# SeccionRF.net
KiCad netlist of a schematic drawn in Altium Designer
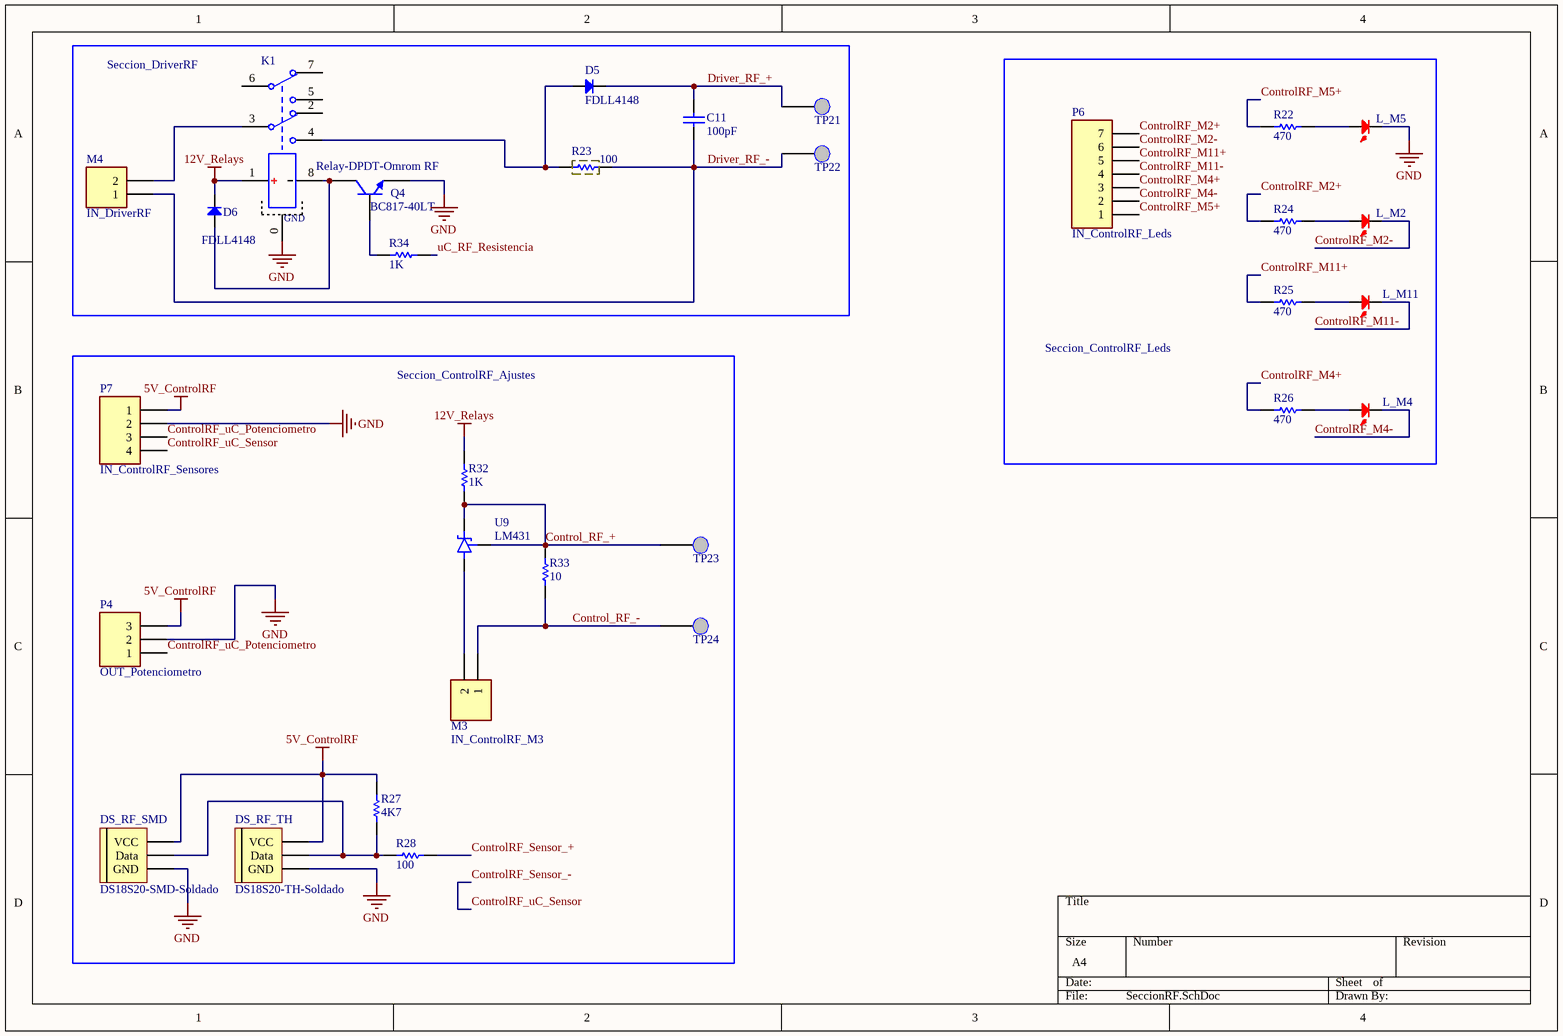
[diagram p0: SeccionRF.SchDoc]

(export (version "E")
  (design (tool "Eeschema 10.0.6"))
  (components
    (comp (ref "C11")
      (value "100pF")
      (footprint "Nahuel_SMD_Body:C_0805")
      (description "CAP CER 100PF 50V C0G/NP0 0805")
      (fields (field (name "PUBLISHER") "Altium Limited"))
      (libsource (lib "Nahuel_SMD_Body") (part "C_100pF"))
    )
    (comp (ref "D5")
      (value "FDLL4148")
      (footprint "Nahuel_SMD_Body:SOD-80/MLL34")
      (description "DIODE GEN PURP 100V 200MA LL34/SOD80/MINI MELF")
      (fields (field (name "PUBLISHER") "Altium Limited"))
      (libsource (lib "Nahuel_SMD_Body") (part "Diode FDLL4148"))
    )
    (comp (ref "D6")
      (value "FDLL4148")
      (footprint "SOD-80/MLL34")
      (description "DIODE GEN PURP 100V 200MA LL34/SOD80/MINI MELF")
      (fields (field (name "PUBLISHER") "Altium Limited"))
      (libsource (lib "Nahuel_SMD_Body") (part "Diode FDLL4148"))
    )
    (comp (ref "DS_RF_SMD")
      (value "DS18S20-SMD-Soldado")
      (footprint "Nahuel_SMD_Body:SOIC8")
      (description "SENSOR DIGITAL -55C-125C 8SOIC")
      (fields (field (name "PUBLISHER") "Altium Limited"))
      (libsource (lib "Nahuel_SMD_Body") (part "DS18S20-SMD-Soldado"))
    )
    (comp (ref "DS_RF_TH")
      (value "DS18S20-TH-Soldado")
      (footprint "Nahuel_TH_BODY:TO92")
      (description "Temperature Sensor Digital, Local -55°C ~ 125°C 8 b TO-92-3")
      (fields (field (name "PUBLISHER") "Altium Limited"))
      (libsource (lib "Nahuel_TH_BODY") (part "DS18S20-TH-Soldado"))
    )
    (comp (ref "K1")
      (value "Relay-DPDT-Omrom RF")
      (footprint "Nahuel_SMD_Body:Relay RF omron")
      (description "RELAY RF DPDT 1A 12V")
      (fields (field (name "PUBLISHER") "Altium Limited"))
      (libsource (lib "Nahuel_SMD_Body") (part "Relay-DPDT-Omrom RF"))
    )
    (comp (ref "L_M2")
      (value "PinesParaLed")
      (footprint "Nahuel_TH_BODY:Jumper-Simple")
      (description "CONN HEADER 2 POS 2.54")
      (fields (field (name "PUBLISHER") "Altium Limited"))
      (libsource (lib "Nahuel_TH_BODY") (part "PinesParaLed"))
    )
    (comp (ref "L_M4")
      (value "PinesParaLed")
      (footprint "Nahuel_TH_BODY:Jumper-Simple")
      (description "CONN HEADER 2 POS 2.54")
      (fields (field (name "PUBLISHER") "Altium Limited"))
      (libsource (lib "Nahuel_TH_BODY") (part "PinesParaLed"))
    )
    (comp (ref "L_M5")
      (value "PinesParaLed")
      (footprint "Nahuel_TH_BODY:Jumper-Simple")
      (description "CONN HEADER 2 POS 2.54")
      (fields (field (name "PUBLISHER") "Altium Limited"))
      (libsource (lib "Nahuel_TH_BODY") (part "PinesParaLed"))
    )
    (comp (ref "L_M11")
      (value "PinesParaLed")
      (footprint "Nahuel_TH_BODY:Jumper-Simple")
      (description "CONN HEADER 2 POS 2.54")
      (fields (field (name "PUBLISHER") "Altium Limited"))
      (libsource (lib "Nahuel_TH_BODY") (part "PinesParaLed"))
    )
    (comp (ref "M3")
      (value "IN_ControlRF_M3")
      (footprint "B2B-XH-A_3D")
      (description "CONN HEADER XH TOP 2POS 2.5MM")
      (fields (field (name "PUBLISHER") "Altium Limited"))
      (libsource (lib "") (part "JST_2.5_2_1"))
    )
    (comp (ref "M4")
      (value "IN_DriverRF")
      (footprint "B2B-XH-A_3D")
      (description "CONN HEADER XH TOP 2POS 2.5MM")
      (fields (field (name "PUBLISHER") "Altium Limited"))
      (libsource (lib "Nahuel_Connectors_BODY") (part "JST_2.5_2"))
    )
    (comp (ref "P4")
      (value "OUT_Potenciometro")
      (footprint "B3B-XH-A_3D")
      (description "CONN HEADER XH TOP 3POS 2.5MM")
      (fields (field (name "PUBLISHER") "Altium Limited"))
      (libsource (lib "Nahuel_Connectors_BODY") (part "JST_2.5_3"))
    )
    (comp (ref "P6")
      (value "IN_ControlRF_Leds")
      (footprint "Nahuel_Connectors_BODY:B7B-XH-A_3D")
      (description "CONN HEADER XH TOP 7POS 2.5MM")
      (fields (field (name "PUBLISHER") "Altium Limited"))
      (libsource (lib "Nahuel_Connectors_BODY") (part "JST_2.5_7"))
    )
    (comp (ref "P7")
      (value "IN_ControlRF_Sensores")
      (footprint "B4B-XH-A_3D")
      (description "CONN HEADER XH TOP 4POS 2.5MM")
      (fields (field (name "PUBLISHER") "Altium Limited"))
      (libsource (lib "Nahuel_Connectors_BODY") (part "JST_2.5_4"))
    )
    (comp (ref "Q4")
      (value "BC817-40LT")
      (footprint "Nahuel_SMD_Body:SOT23")
      (description "TRANS NPN 45V 0.5A SOT23")
      (fields (field (name "PUBLISHER") "Altium Limited"))
      (libsource (lib "Nahuel_SMD_Body") (part "BC817"))
    )
    (comp (ref "R22")
      (value "470")
      (footprint "Nahuel_SMD_Body:R_0805")
      (description "RES SMD 470 OHM 1% 1/8W 0805")
      (fields (field (name "PUBLISHER") "Altium Limited"))
      (libsource (lib "Nahuel_SMD_Body") (part "R_470"))
    )
    (comp (ref "R23")
      (value "100")
      (footprint "Nahuel_TH_BODY:R 10W")
      (description "RES 100 OHM 10W 5% AXIAL")
      (fields (field (name "PUBLISHER") "Altium Limited"))
      (libsource (lib "Nahuel_TH_BODY") (part "Resistor-10W"))
    )
    (comp (ref "R24")
      (value "470")
      (footprint "Nahuel_SMD_Body:R_0805")
      (description "RES SMD 470 OHM 1% 1/8W 0805")
      (fields (field (name "PUBLISHER") "Altium Limited"))
      (libsource (lib "Nahuel_SMD_Body") (part "R_470"))
    )
    (comp (ref "R25")
      (value "470")
      (footprint "Nahuel_SMD_Body:R_0805")
      (description "RES SMD 470 OHM 1% 1/8W 0805")
      (fields (field (name "PUBLISHER") "Altium Limited"))
      (libsource (lib "Nahuel_SMD_Body") (part "R_470"))
    )
    (comp (ref "R26")
      (value "470")
      (footprint "Nahuel_SMD_Body:R_0805")
      (description "RES SMD 470 OHM 1% 1/8W 0805")
      (fields (field (name "PUBLISHER") "Altium Limited"))
      (libsource (lib "Nahuel_SMD_Body") (part "R_470"))
    )
    (comp (ref "R27")
      (value "4K7")
      (footprint "Nahuel_SMD_Body:R_0805")
      (description "RES SMD 4K7 OHM 1% 1/8W 0805")
      (fields (field (name "PUBLISHER") "Altium Limited"))
      (libsource (lib "Nahuel_SMD_Body") (part "R_4k7"))
    )
    (comp (ref "R28")
      (value "100")
      (footprint "Nahuel_SMD_Body:R_0805")
      (description "RES SMD 100 OHM 1% 1/8W 0805")
      (fields (field (name "PUBLISHER") "Altium Limited"))
      (libsource (lib "Nahuel_SMD_Body") (part "R_100"))
    )
    (comp (ref "R32")
      (value "1K")
      (footprint "Nahuel_SMD_Body:R_0805")
      (description "RES SMD 1K OHM 1% 1/8W 0805")
      (fields (field (name "PUBLISHER") "Altium Limited"))
      (libsource (lib "Nahuel_SMD_Body") (part "R_1k"))
    )
    (comp (ref "R33")
      (value "10")
      (footprint "Nahuel_SMD_Body:R_0805")
      (description "RES SMD 10 OHM 1% 1/8W 0805")
      (fields (field (name "PUBLISHER") "Altium Limited"))
      (libsource (lib "Nahuel_SMD_Body") (part "R_10"))
    )
    (comp (ref "R34")
      (value "1K")
      (footprint "Nahuel_SMD_Body:R_0805")
      (description "RES SMD 1K OHM 1% 1/8W 0805")
      (fields (field (name "PUBLISHER") "Altium Limited"))
      (libsource (lib "Nahuel_SMD_Body") (part "R_1k"))
    )
    (comp (ref "TP21")
      (value "DRF+")
      (footprint "Nahuel_TH_BODY:TP-5002")
      (fields (field (name "PUBLISHER") "Altium Limited"))
      (libsource (lib "Nahuel_TH_BODY") (part "TestPoint"))
    )
    (comp (ref "TP22")
      (value "DRF-")
      (footprint "Nahuel_TH_BODY:TP-5002")
      (fields (field (name "PUBLISHER") "Altium Limited"))
      (libsource (lib "Nahuel_TH_BODY") (part "TestPoint"))
    )
    (comp (ref "TP23")
      (value "CRF+")
      (footprint "Nahuel_TH_BODY:TP-5002")
      (fields (field (name "PUBLISHER") "Altium Limited"))
      (libsource (lib "Nahuel_TH_BODY") (part "TestPoint"))
    )
    (comp (ref "TP24")
      (value "CRF-")
      (footprint "Nahuel_TH_BODY:TP-5002")
      (fields (field (name "PUBLISHER") "Altium Limited"))
      (libsource (lib "Nahuel_TH_BODY") (part "TestPoint"))
    )
    (comp (ref "U9")
      (value "LM431")
      (footprint "Nahuel_SMD_Body:SOT89")
      (description "IC VREF SHUNT 36V 1% SOT89-3")
      (fields (field (name "PUBLISHER") "Altium Limited"))
      (libsource (lib "Nahuel_SMD_Body") (part "LM431"))
    )
  )
  (nets
    (net (code "1") (name "/ControlRF_M2+") (class "Default")
      (node (ref "P6") (pin "7") (pinfunction "7_7") (pintype "passive"))
      (node (ref "R24") (pin "1") (pinfunction "1_1") (pintype "passive"))
    )
    (net (code "2") (name "/ControlRF_M2-") (class "Default")
      (node (ref "L_M2") (pin "2") (pinfunction "2_2") (pintype "passive"))
      (node (ref "P6") (pin "6") (pinfunction "6_6") (pintype "passive"))
    )
    (net (code "3") (name "/ControlRF_M4+") (class "Default")
      (node (ref "P6") (pin "3") (pinfunction "3_3") (pintype "passive"))
      (node (ref "R26") (pin "1") (pinfunction "1_1") (pintype "passive"))
    )
    (net (code "4") (name "/ControlRF_M4-") (class "Default")
      (node (ref "L_M4") (pin "2") (pinfunction "2_2") (pintype "passive"))
      (node (ref "P6") (pin "2") (pinfunction "2_2") (pintype "passive"))
    )
    (net (code "5") (name "/ControlRF_M5+") (class "Default")
      (node (ref "P6") (pin "1") (pinfunction "1_1") (pintype "passive"))
      (node (ref "R22") (pin "1") (pinfunction "1_1") (pintype "passive"))
    )
    (net (code "6") (name "/ControlRF_M11+") (class "Default")
      (node (ref "P6") (pin "5") (pinfunction "5_5") (pintype "passive"))
      (node (ref "R25") (pin "1") (pinfunction "1_1") (pintype "passive"))
    )
    (net (code "7") (name "/ControlRF_M11-") (class "Default")
      (node (ref "L_M11") (pin "2") (pinfunction "2_2") (pintype "passive"))
      (node (ref "P6") (pin "4") (pinfunction "4_4") (pintype "passive"))
    )
    (net (code "8") (name "/ControlRF_Sensor_+") (class "Default")
      (node (ref "R28") (pin "2") (pinfunction "2_2") (pintype "passive"))
    )
    (net (code "9") (name "/ControlRF_Sensor_-") (class "Default")
      (node (ref "P7") (pin "4") (pinfunction "4_4") (pintype "passive"))
    )
    (net (code "10") (name "/ControlRF_uC_Potenciometro") (class "Default")
      (node (ref "P4") (pin "1") (pinfunction "1_1") (pintype "passive"))
      (node (ref "P7") (pin "3") (pinfunction "3_3") (pintype "passive"))
    )
    (net (code "11") (name "/Control_RF_+") (class "Default")
      (node (ref "R32") (pin "1") (pinfunction "1_1") (pintype "passive"))
      (node (ref "R33") (pin "2") (pinfunction "2_2") (pintype "passive"))
      (node (ref "TP23") (pin "1") (pinfunction "1_1") (pintype "passive"))
      (node (ref "U9") (pin "1") (pinfunction "R_1") (pintype "passive"))
      (node (ref "U9") (pin "3") (pinfunction "K_3") (pintype "passive"))
    )
    (net (code "12") (name "/Control_RF_-") (class "Default")
      (node (ref "M3") (pin "1") (pinfunction "1_1") (pintype "passive"))
      (node (ref "R33") (pin "1") (pinfunction "1_1") (pintype "passive"))
      (node (ref "TP24") (pin "1") (pinfunction "1_1") (pintype "passive"))
    )
    (net (code "13") (name "/Driver_RF_+") (class "Default")
      (node (ref "C11") (pin "2") (pinfunction "2_2") (pintype "passive"))
      (node (ref "D5") (pin "2") (pinfunction "K_2") (pintype "passive"))
      (node (ref "TP21") (pin "1") (pinfunction "1_1") (pintype "passive"))
    )
    (net (code "14") (name "/Driver_RF_-") (class "Default")
      (node (ref "C11") (pin "1") (pinfunction "1_1") (pintype "passive"))
      (node (ref "M4") (pin "1") (pinfunction "1_1") (pintype "passive"))
      (node (ref "R23") (pin "2") (pinfunction "2_2") (pintype "passive"))
      (node (ref "TP22") (pin "1") (pinfunction "1_1") (pintype "passive"))
    )
    (net (code "15") (name "/uC_RF_Resistencia") (class "Default")
      (node (ref "R34") (pin "1") (pinfunction "1_1") (pintype "passive"))
    )
    (net (code "16") (name "5V_ControlRF") (class "Default")
      (node (ref "DS_RF_SMD") (pin "3") (pinfunction "VCC_3") (pintype "passive"))
      (node (ref "DS_RF_TH") (pin "3") (pinfunction "VCC_3") (pintype "passive"))
      (node (ref "P4") (pin "3") (pinfunction "3_3") (pintype "passive"))
      (node (ref "P7") (pin "1") (pinfunction "1_1") (pintype "passive"))
      (node (ref "R27") (pin "2") (pinfunction "2_2") (pintype "passive"))
    )
    (net (code "17") (name "12V_Relays") (class "Default")
      (node (ref "D6") (pin "2") (pinfunction "K_2") (pintype "passive"))
      (node (ref "K1") (pin "1") (pinfunction "+_1") (pintype "passive"))
      (node (ref "R32") (pin "2") (pinfunction "2_2") (pintype "passive"))
    )
    (net (code "18") (name "GND") (class "Default")
      (node (ref "DS_RF_SMD") (pin "5") (pinfunction "GND_5") (pintype "passive"))
      (node (ref "DS_RF_TH") (pin "1") (pinfunction "GND_1") (pintype "passive"))
      (node (ref "K1") (pin "0") (pinfunction "GND_0") (pintype "passive"))
      (node (ref "L_M5") (pin "2") (pinfunction "2_2") (pintype "passive"))
      (node (ref "P4") (pin "2") (pinfunction "2_2") (pintype "passive"))
      (node (ref "P7") (pin "2") (pinfunction "2_2") (pintype "passive"))
      (node (ref "Q4") (pin "2") (pinfunction "E_2") (pintype "passive"))
    )
    (net (code "19") (name "Net-(D5-A)") (class "Default")
      (node (ref "D5") (pin "1") (pinfunction "A_1") (pintype "passive"))
      (node (ref "K1") (pin "4") (pinfunction "NOa_4") (pintype "passive"))
      (node (ref "R23") (pin "1") (pinfunction "1_1") (pintype "passive"))
    )
    (net (code "20") (name "Net-(D6-A)") (class "Default")
      (node (ref "D6") (pin "1") (pinfunction "A_1") (pintype "passive"))
      (node (ref "K1") (pin "8") (pinfunction "-_8") (pintype "passive"))
      (node (ref "Q4") (pin "3") (pinfunction "C_3") (pintype "passive"))
    )
    (net (code "21") (name "Net-(DS_RF_SMD-Data)") (class "Default")
      (node (ref "DS_RF_SMD") (pin "4") (pinfunction "Data_4") (pintype "passive"))
      (node (ref "DS_RF_TH") (pin "2") (pinfunction "Data_2") (pintype "passive"))
      (node (ref "R27") (pin "1") (pinfunction "1_1") (pintype "passive"))
      (node (ref "R28") (pin "1") (pinfunction "1_1") (pintype "passive"))
    )
    (net (code "22") (name "Net-(K1-Ca)") (class "Default")
      (node (ref "K1") (pin "3") (pinfunction "Ca_3") (pintype "passive"))
      (node (ref "M4") (pin "2") (pinfunction "2_2") (pintype "passive"))
    )
    (net (code "23") (name "Net-(L_M2-Pad1)") (class "Default")
      (node (ref "L_M2") (pin "1") (pinfunction "1_1") (pintype "passive"))
      (node (ref "R24") (pin "2") (pinfunction "2_2") (pintype "passive"))
    )
    (net (code "24") (name "Net-(L_M4-Pad1)") (class "Default")
      (node (ref "L_M4") (pin "1") (pinfunction "1_1") (pintype "passive"))
      (node (ref "R26") (pin "2") (pinfunction "2_2") (pintype "passive"))
    )
    (net (code "25") (name "Net-(L_M5-Pad1)") (class "Default")
      (node (ref "L_M5") (pin "1") (pinfunction "1_1") (pintype "passive"))
      (node (ref "R22") (pin "2") (pinfunction "2_2") (pintype "passive"))
    )
    (net (code "26") (name "Net-(L_M11-Pad1)") (class "Default")
      (node (ref "L_M11") (pin "1") (pinfunction "1_1") (pintype "passive"))
      (node (ref "R25") (pin "2") (pinfunction "2_2") (pintype "passive"))
    )
    (net (code "27") (name "Net-(Q4-B)") (class "Default")
      (node (ref "Q4") (pin "1") (pinfunction "B_1") (pintype "passive"))
      (node (ref "R34") (pin "2") (pinfunction "2_2") (pintype "passive"))
    )
    (net (code "28") (name "Net-(U9-A)") (class "Default")
      (node (ref "M3") (pin "2") (pinfunction "2_2") (pintype "passive"))
      (node (ref "U9") (pin "2") (pinfunction "A_2") (pintype "passive"))
    )
    (net (code "29") (name "unconnected-(K1-Cb-Pad6)") (class "Default")
      (node (ref "K1") (pin "6") (pinfunction "Cb_6") (pintype "passive"))
    )
    (net (code "30") (name "unconnected-(K1-NCa-Pad2)") (class "Default")
      (node (ref "K1") (pin "2") (pinfunction "NCa_2") (pintype "passive"))
    )
    (net (code "31") (name "unconnected-(K1-NCb-Pad7)") (class "Default")
      (node (ref "K1") (pin "7") (pinfunction "NCb_7") (pintype "passive"))
    )
    (net (code "32") (name "unconnected-(K1-NOb-Pad5)") (class "Default")
      (node (ref "K1") (pin "5") (pinfunction "NOb_5") (pintype "passive"))
    )
  )
)
